# IR2110.net
KiCad netlist of a schematic drawn in Altium Designer
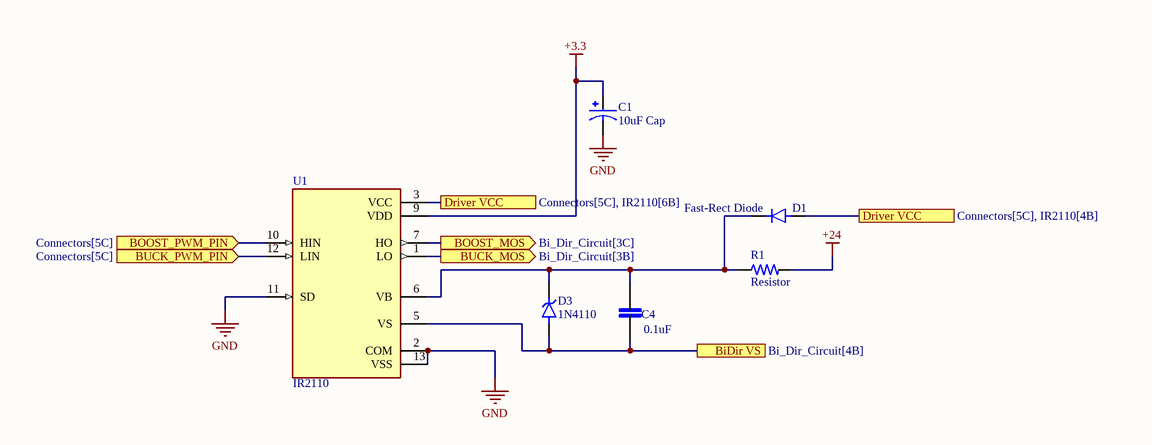
[diagram p0: IR2110.SchDoc]

(export (version "E")
  (design (tool "Eeschema 10.0.6"))
  (components
    (comp (ref "C1")
      (value "10uF Cap")
      (footprint "CAP_10uF")
      (description "CAP ALUM 10UF 20% 50V RADIAL")
      (fields (field (name "MP") "ECE-A1HN100UI") (field (name "MF") "Panasonic"))
      (libsource (lib "MySCH_Library") (part "10uF Cap"))
    )
    (comp (ref "C4")
      (value "0.1uF")
      (footprint "Ceramic Capacitor")
      (fields (field (name "MP") "LD051A121KAB2A") (field (name "MF") "AVX"))
      (libsource (lib "Capacitors Through Hole") (part "Ceramic Capacitor"))
    )
    (comp (ref "D1")
      (value "Fast-Rect Diode")
      (footprint "Common Trhough Hole")
      (fields (field (name "MF") "NTE Electronics, Inc.") (field (name "MP") "1N4007"))
      (libsource (lib "Diodes Through Hole") (part "Normal Diode"))
    )
    (comp (ref "D3")
      (value "1N4110")
      (footprint "Common Trhough Hole")
      (fields (field (name "MP") "1SMA5926") (field (name "MF") "Taiwan Semiconductor"))
      (libsource (lib "Diodes Through Hole") (part "Zener Diode"))
    )
    (comp (ref "R1")
      (value "Resistor")
      (footprint "Resistor_Through Hole")
      (fields
        (field (name "MP") "2-2176053-0")
        (field (name "TOLERANCE") "1%")
        (field (name "MF") "TE Connectivity")
      )
      (libsource (lib "Resistors Through Hole") (part "Resistor"))
    )
    (comp (ref "U1")
      (value "IR2110")
      (footprint "IR2110")
      (description "Half-Bridge Gate Driver IC Non-Inverting 16-SOIC")
      (fields (field (name "MF") "Infineon"))
      (libsource (lib "MySCH_Library") (part "IR2110"))
    )
  )
  (nets
    (net (code "1") (name "+3.3") (class "Default")
      (node (ref "C1") (pin "P") (pinfunction "P_P") (pintype "passive"))
      (node (ref "U1") (pin "9") (pinfunction "VDD_9") (pintype "power_in"))
    )
    (net (code "2") (name "+24") (class "Default")
      (node (ref "R1") (pin "2") (pinfunction "2_2") (pintype "passive"))
    )
    (net (code "3") (name "/BOOST_MOS") (class "Default")
      (node (ref "U1") (pin "7") (pinfunction "HO_7") (pintype "output"))
    )
    (net (code "4") (name "/BOOST_PWM_PIN") (class "Default")
      (node (ref "U1") (pin "10") (pinfunction "HIN_10") (pintype "input"))
    )
    (net (code "5") (name "/BUCK_MOS") (class "Default")
      (node (ref "U1") (pin "1") (pinfunction "LO_1") (pintype "output"))
    )
    (net (code "6") (name "/BUCK_PWM_PIN") (class "Default")
      (node (ref "U1") (pin "12") (pinfunction "LIN_12") (pintype "input"))
    )
    (net (code "7") (name "/BiDir VS") (class "Default")
      (node (ref "C4") (pin "1") (pinfunction "1_1") (pintype "passive"))
      (node (ref "D3") (pin "2") (pinfunction "A_2") (pintype "passive"))
      (node (ref "U1") (pin "5") (pinfunction "VS_5") (pintype "passive"))
    )
    (net (code "8") (name "/Driver VCC") (class "Default")
      (node (ref "D1") (pin "2") (pinfunction "A_2") (pintype "passive"))
      (node (ref "U1") (pin "3") (pinfunction "VCC_3") (pintype "power_in"))
    )
    (net (code "9") (name "GND") (class "Default")
      (node (ref "C1") (pin "N") (pinfunction "N_N") (pintype "passive"))
      (node (ref "U1") (pin "11") (pinfunction "SD_11") (pintype "input"))
      (node (ref "U1") (pin "13") (pinfunction "VSS_13") (pintype "power_in"))
      (node (ref "U1") (pin "2") (pinfunction "COM_2") (pintype "power_in"))
    )
    (net (code "10") (name "Net-(D1-K)") (class "Default")
      (node (ref "C4") (pin "2") (pinfunction "2_2") (pintype "passive"))
      (node (ref "D1") (pin "1") (pinfunction "K_1") (pintype "passive"))
      (node (ref "D3") (pin "1") (pinfunction "K_1") (pintype "passive"))
      (node (ref "R1") (pin "1") (pinfunction "1_1") (pintype "passive"))
      (node (ref "U1") (pin "6") (pinfunction "VB_6") (pintype "passive"))
    )
  )
)
